# Stepper_Controller_Schematic.net
KiCad netlist of a schematic drawn in Altium Designer
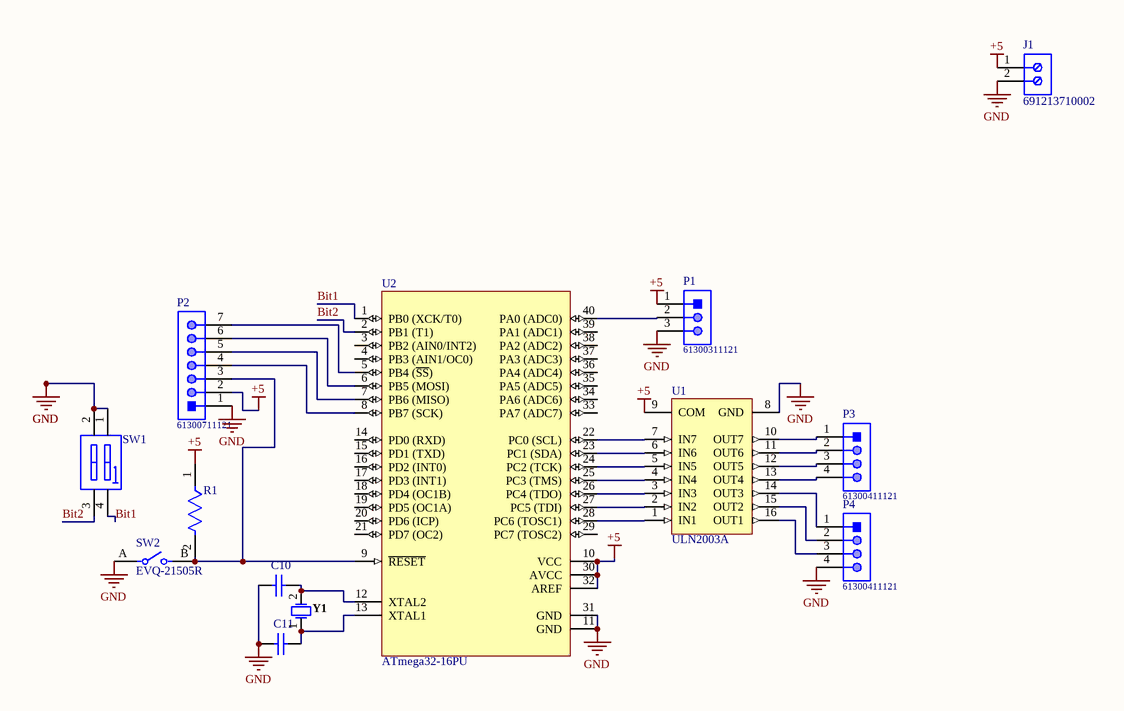
[diagram p0: Stepper Controller Schematic.SchDoc]

(export (version "E")
  (design (tool "Eeschema 10.0.6"))
  (components
    (comp (ref "C10")
      (value "~")
      (footprint "CAPR51-254-508X318X736")
      (libsource (lib "Altium Content Vault") (part "CAP-NP-2"))
    )
    (comp (ref "C11")
      (value "~")
      (footprint "CAPR51-254-508X318X736")
      (libsource (lib "Altium Content Vault") (part "CAP-NP-2"))
    )
    (comp (ref "J1")
      (value "691213710002")
      (footprint "691213710002")
      (description "Serie 213 - 5.00 mm Horizontal Entry Modular with RisingCage Clamp WR-TBL, 2 pin")
      (fields (field (name "MANUFACTURER") "Wurth Elektronik") (field (name "PUBLISHER") "WurthElektronik"))
      (libsource (lib "Altium Content Vault") (part "WE-CN-1P-F-TB2"))
    )
    (comp (ref "P1")
      (value "61300311121")
      (footprint "61300311121")
      (description "THT Vertical Pin Header WR-PHD, Pitch 2.54 mm, Single Row, 3 pins")
      (fields (field (name "MANUFACTURER") "Wurth Elektronik") (field (name "PUBLISHER") "WurthElektronik"))
      (libsource (lib "Altium Content Vault") (part "WE-CN-1P-M-R3"))
    )
    (comp (ref "P2")
      (value "61300711121")
      (footprint "61300711121")
      (description "THT Vertical Pin Header WR-PHD, Pitch 2.54 mm, Single Row, 7 pins")
      (fields (field (name "MANUFACTURER") "Wurth Elektronik") (field (name "PUBLISHER") "WurthElektronik"))
      (libsource (lib "Altium Content Vault") (part "WE-CN-1P-M-R7"))
    )
    (comp (ref "P3")
      (value "61300411121")
      (footprint "61300411121")
      (description "THT Vertical Pin Header WR-PHD, Pitch 2.54 mm, Single Row, 4 pins")
      (fields (field (name "MANUFACTURER") "Wurth Elektronik") (field (name "PUBLISHER") "WurthElektronik"))
      (libsource (lib "Altium Content Vault") (part "WE-CN-1P-M-R4"))
    )
    (comp (ref "P4")
      (value "61300411121")
      (footprint "61300411121")
      (description "THT Vertical Pin Header WR-PHD, Pitch 2.54 mm, Single Row, 4 pins")
      (fields (field (name "MANUFACTURER") "Wurth Elektronik") (field (name "PUBLISHER") "WurthElektronik"))
      (libsource (lib "Altium Content Vault") (part "WE-CN-1P-M-R4"))
    )
    (comp (ref "R1")
      (value "~")
      (footprint "FP-CF14-MFG")
      (description "RES 7.5K OHM 1/4W 5% AXIAL")
      (fields (field (name "TOLERANCE") "5%"))
      (libsource (lib "Altium Content Vault") (part "1029c3af85768c4190bb7ad29bc67b5"))
    )
    (comp (ref "SW1")
      (value "~")
      (footprint "418117270902")
      (description "WS-DITV 2.54 mm Compact THT Dip Switch with Raised Actuator")
      (fields (field (name "MANUFACTURER") "Wuerth Elektronik") (field (name "PARTNUMBER") "418117270902"))
      (libsource (lib "Altium Content Vault") (part "WE-DIP-SW-4"))
    )
    (comp (ref "SW2")
      (value "EVQ-21505R")
      (footprint "FP-EVQ-21505R-MFG")
      (description "SWITCH TACTILE SPST-NO 0.02A 15V")
      (libsource (lib "Altium Content Vault") (part "2b0b2b19372efd94fa7681498149756"))
    )
    (comp (ref "U1")
      (value "ULN2003A")
      (footprint "STM-DIP-16L")
      (description "Seven Darlington Array, 50 V, 0.5 A, -40 to 85 degC, 16-Pin DIP, RoHS, Tube")
      (fields (field (name "MANUFACTURER") "STMicroelectronics"))
      (libsource (lib "Altium Content Vault") (part "STM-ULN2003A-PDIP-16"))
    )
    (comp (ref "U2")
      (value "ATmega32-16PU")
      (footprint "40P6")
      (libsource (lib "Altium Content Vault") (part "MC-8B-ATM32-IL40"))
    )
    (comp (ref "Y1")
      (value "~")
      (footprint "FOX-FOXSLF160-20")
      (description "Resistance Weld Thru-Hole Crystal, 16 MHz, -20 to 70 degC, 2-Pin THD, RoHS, Bulk")
      (fields (field (name "TOLERANCE") "1%"))
      (libsource (lib "Altium Content Vault") (part "XTAL-1-2-2"))
    )
  )
  (nets
    (net (code "1") (name "+5") (class "Default")
      (node (ref "J1") (pin "1") (pinfunction "1_1") (pintype "passive"))
      (node (ref "P1") (pin "1") (pinfunction "1_1") (pintype "passive"))
      (node (ref "P2") (pin "2") (pinfunction "2_2") (pintype "passive"))
      (node (ref "R1") (pin "1") (pinfunction "1_1") (pintype "passive"))
      (node (ref "U1") (pin "9") (pinfunction "COM_9") (pintype "passive"))
      (node (ref "U2") (pin "10") (pinfunction "VCC_10") (pintype "power_in"))
      (node (ref "U2") (pin "30") (pinfunction "AVCC_30") (pintype "power_in"))
      (node (ref "U2") (pin "32") (pinfunction "AREF_32") (pintype "passive"))
    )
    (net (code "2") (name "/Bit1") (class "Default")
      (node (ref "SW1") (pin "4") (pinfunction "4_4") (pintype "passive"))
      (node (ref "U2") (pin "1") (pinfunction "PB0_(XCK/T0)_1") (pintype "bidirectional"))
    )
    (net (code "3") (name "/Bit2") (class "Default")
      (node (ref "SW1") (pin "3") (pinfunction "3_3") (pintype "passive"))
      (node (ref "U2") (pin "2") (pinfunction "PB1_(T1)_2") (pintype "bidirectional"))
    )
    (net (code "4") (name "GND") (class "Default")
      (node (ref "C10") (pin "1") (pinfunction "1_1") (pintype "passive"))
      (node (ref "C11") (pin "1") (pinfunction "1_1") (pintype "passive"))
      (node (ref "J1") (pin "2") (pinfunction "2_2") (pintype "passive"))
      (node (ref "P1") (pin "3") (pinfunction "3_3") (pintype "passive"))
      (node (ref "P2") (pin "1") (pinfunction "1_1") (pintype "passive"))
      (node (ref "P4") (pin "4") (pinfunction "4_4") (pintype "passive"))
      (node (ref "SW1") (pin "1") (pinfunction "1_1") (pintype "passive"))
      (node (ref "SW1") (pin "2") (pinfunction "2_2") (pintype "passive"))
      (node (ref "SW2") (pin "A") (pinfunction "A_A") (pintype "passive"))
      (node (ref "U1") (pin "8") (pinfunction "GND_8") (pintype "power_in"))
      (node (ref "U2") (pin "11") (pinfunction "GND_11") (pintype "power_in"))
      (node (ref "U2") (pin "31") (pinfunction "GND_31") (pintype "power_in"))
    )
    (net (code "5") (name "Net-(U1-IN1)") (class "Default")
      (node (ref "U1") (pin "1") (pinfunction "IN1_1") (pintype "input"))
      (node (ref "U2") (pin "28") (pinfunction "PC6_(TOSC1)_28") (pintype "bidirectional"))
    )
    (net (code "6") (name "Net-(U1-IN2)") (class "Default")
      (node (ref "U1") (pin "2") (pinfunction "IN2_2") (pintype "input"))
      (node (ref "U2") (pin "27") (pinfunction "PC5_(TDI)_27") (pintype "bidirectional"))
    )
    (net (code "7") (name "Net-(U1-IN3)") (class "Default")
      (node (ref "U1") (pin "3") (pinfunction "IN3_3") (pintype "input"))
      (node (ref "U2") (pin "26") (pinfunction "PC4_(TDO)_26") (pintype "bidirectional"))
    )
    (net (code "8") (name "Net-(U1-IN4)") (class "Default")
      (node (ref "U1") (pin "4") (pinfunction "IN4_4") (pintype "input"))
      (node (ref "U2") (pin "25") (pinfunction "PC3_(TMS)_25") (pintype "bidirectional"))
    )
    (net (code "9") (name "Net-(U1-IN5)") (class "Default")
      (node (ref "U1") (pin "5") (pinfunction "IN5_5") (pintype "input"))
      (node (ref "U2") (pin "24") (pinfunction "PC2_(TCK)_24") (pintype "bidirectional"))
    )
    (net (code "10") (name "Net-(U1-IN6)") (class "Default")
      (node (ref "U1") (pin "6") (pinfunction "IN6_6") (pintype "input"))
      (node (ref "U2") (pin "23") (pinfunction "PC1_(SDA)_23") (pintype "bidirectional"))
    )
    (net (code "11") (name "Net-(U1-IN7)") (class "Default")
      (node (ref "U1") (pin "7") (pinfunction "IN7_7") (pintype "input"))
      (node (ref "U2") (pin "22") (pinfunction "PC0_(SCL)_22") (pintype "bidirectional"))
    )
    (net (code "12") (name "Net-(U1-OUT1)") (class "Default")
      (node (ref "P4") (pin "3") (pinfunction "3_3") (pintype "passive"))
      (node (ref "U1") (pin "16") (pinfunction "OUT1_16") (pintype "output"))
    )
    (net (code "13") (name "Net-(U1-OUT2)") (class "Default")
      (node (ref "P4") (pin "2") (pinfunction "2_2") (pintype "passive"))
      (node (ref "U1") (pin "15") (pinfunction "OUT2_15") (pintype "output"))
    )
    (net (code "14") (name "Net-(U1-OUT3)") (class "Default")
      (node (ref "P4") (pin "1") (pinfunction "1_1") (pintype "passive"))
      (node (ref "U1") (pin "14") (pinfunction "OUT3_14") (pintype "output"))
    )
    (net (code "15") (name "Net-(U1-OUT4)") (class "Default")
      (node (ref "P3") (pin "4") (pinfunction "4_4") (pintype "passive"))
      (node (ref "U1") (pin "13") (pinfunction "OUT4_13") (pintype "output"))
    )
    (net (code "16") (name "Net-(U1-OUT5)") (class "Default")
      (node (ref "P3") (pin "3") (pinfunction "3_3") (pintype "passive"))
      (node (ref "U1") (pin "12") (pinfunction "OUT5_12") (pintype "output"))
    )
    (net (code "17") (name "Net-(U1-OUT6)") (class "Default")
      (node (ref "P3") (pin "2") (pinfunction "2_2") (pintype "passive"))
      (node (ref "U1") (pin "11") (pinfunction "OUT6_11") (pintype "output"))
    )
    (net (code "18") (name "Net-(U1-OUT7)") (class "Default")
      (node (ref "P3") (pin "1") (pinfunction "1_1") (pintype "passive"))
      (node (ref "U1") (pin "10") (pinfunction "OUT7_10") (pintype "output"))
    )
    (net (code "19") (name "Net-(U2-PA0_(ADC0))") (class "Default")
      (node (ref "P1") (pin "2") (pinfunction "2_2") (pintype "passive"))
      (node (ref "U2") (pin "40") (pinfunction "PA0_(ADC0)_40") (pintype "bidirectional"))
    )
    (net (code "20") (name "Net-(U2-PB4_(~{SS}))") (class "Default")
      (node (ref "P2") (pin "7") (pinfunction "7_7") (pintype "passive"))
      (node (ref "U2") (pin "5") (pinfunction "PB4_(~{SS})_5") (pintype "bidirectional"))
    )
    (net (code "21") (name "Net-(U2-PB5_(MOSI))") (class "Default")
      (node (ref "P2") (pin "6") (pinfunction "6_6") (pintype "passive"))
      (node (ref "U2") (pin "6") (pinfunction "PB5_(MOSI)_6") (pintype "bidirectional"))
    )
    (net (code "22") (name "Net-(U2-PB6_(MISO))") (class "Default")
      (node (ref "P2") (pin "5") (pinfunction "5_5") (pintype "passive"))
      (node (ref "U2") (pin "7") (pinfunction "PB6_(MISO)_7") (pintype "bidirectional"))
    )
    (net (code "23") (name "Net-(U2-PB7_(SCK))") (class "Default")
      (node (ref "P2") (pin "4") (pinfunction "4_4") (pintype "passive"))
      (node (ref "U2") (pin "8") (pinfunction "PB7_(SCK)_8") (pintype "bidirectional"))
    )
    (net (code "24") (name "Net-(U2-XTAL1)") (class "Default")
      (node (ref "C11") (pin "2") (pinfunction "2_2") (pintype "passive"))
      (node (ref "U2") (pin "13") (pinfunction "XTAL1_13") (pintype "passive"))
      (node (ref "Y1") (pin "1") (pinfunction "1_1") (pintype "passive"))
    )
    (net (code "25") (name "Net-(U2-XTAL2)") (class "Default")
      (node (ref "C10") (pin "2") (pinfunction "2_2") (pintype "passive"))
      (node (ref "U2") (pin "12") (pinfunction "XTAL2_12") (pintype "passive"))
      (node (ref "Y1") (pin "2") (pinfunction "2_2") (pintype "passive"))
    )
    (net (code "26") (name "Net-(U2-~{RESET})") (class "Default")
      (node (ref "P2") (pin "3") (pinfunction "3_3") (pintype "passive"))
      (node (ref "R1") (pin "2") (pinfunction "2_2") (pintype "passive"))
      (node (ref "SW2") (pin "B") (pinfunction "B_B") (pintype "passive"))
      (node (ref "U2") (pin "9") (pinfunction "~{RESET}_9") (pintype "input"))
    )
    (net (code "27") (name "unconnected-(U2-PA1_(ADC1)-Pad39)") (class "Default")
      (node (ref "U2") (pin "39") (pinfunction "PA1_(ADC1)_39") (pintype "bidirectional"))
    )
    (net (code "28") (name "unconnected-(U2-PA2_(ADC2)-Pad38)") (class "Default")
      (node (ref "U2") (pin "38") (pinfunction "PA2_(ADC2)_38") (pintype "bidirectional"))
    )
    (net (code "29") (name "unconnected-(U2-PA3_(ADC3)-Pad37)") (class "Default")
      (node (ref "U2") (pin "37") (pinfunction "PA3_(ADC3)_37") (pintype "bidirectional"))
    )
    (net (code "30") (name "unconnected-(U2-PA4_(ADC4)-Pad36)") (class "Default")
      (node (ref "U2") (pin "36") (pinfunction "PA4_(ADC4)_36") (pintype "bidirectional"))
    )
    (net (code "31") (name "unconnected-(U2-PA5_(ADC5)-Pad35)") (class "Default")
      (node (ref "U2") (pin "35") (pinfunction "PA5_(ADC5)_35") (pintype "bidirectional"))
    )
    (net (code "32") (name "unconnected-(U2-PA6_(ADC6)-Pad34)") (class "Default")
      (node (ref "U2") (pin "34") (pinfunction "PA6_(ADC6)_34") (pintype "bidirectional"))
    )
    (net (code "33") (name "unconnected-(U2-PA7_(ADC7)-Pad33)") (class "Default")
      (node (ref "U2") (pin "33") (pinfunction "PA7_(ADC7)_33") (pintype "bidirectional"))
    )
    (net (code "34") (name "unconnected-(U2-PB2_(AIN0{slash}INT2)-Pad3)") (class "Default")
      (node (ref "U2") (pin "3") (pinfunction "PB2_(AIN0/INT2)_3") (pintype "bidirectional"))
    )
    (net (code "35") (name "unconnected-(U2-PB3_(AIN1{slash}OC0)-Pad4)") (class "Default")
      (node (ref "U2") (pin "4") (pinfunction "PB3_(AIN1/OC0)_4") (pintype "bidirectional"))
    )
    (net (code "36") (name "unconnected-(U2-PC7_(TOSC2)-Pad29)") (class "Default")
      (node (ref "U2") (pin "29") (pinfunction "PC7_(TOSC2)_29") (pintype "bidirectional"))
    )
    (net (code "37") (name "unconnected-(U2-PD0_(RXD)-Pad14)") (class "Default")
      (node (ref "U2") (pin "14") (pinfunction "PD0_(RXD)_14") (pintype "bidirectional"))
    )
    (net (code "38") (name "unconnected-(U2-PD1_(TXD)-Pad15)") (class "Default")
      (node (ref "U2") (pin "15") (pinfunction "PD1_(TXD)_15") (pintype "bidirectional"))
    )
    (net (code "39") (name "unconnected-(U2-PD2_(INT0)-Pad16)") (class "Default")
      (node (ref "U2") (pin "16") (pinfunction "PD2_(INT0)_16") (pintype "bidirectional"))
    )
    (net (code "40") (name "unconnected-(U2-PD3_(INT1)-Pad17)") (class "Default")
      (node (ref "U2") (pin "17") (pinfunction "PD3_(INT1)_17") (pintype "bidirectional"))
    )
    (net (code "41") (name "unconnected-(U2-PD4_(OC1B)-Pad18)") (class "Default")
      (node (ref "U2") (pin "18") (pinfunction "PD4_(OC1B)_18") (pintype "bidirectional"))
    )
    (net (code "42") (name "unconnected-(U2-PD5_(OC1A)-Pad19)") (class "Default")
      (node (ref "U2") (pin "19") (pinfunction "PD5_(OC1A)_19") (pintype "bidirectional"))
    )
    (net (code "43") (name "unconnected-(U2-PD6_(ICP)-Pad20)") (class "Default")
      (node (ref "U2") (pin "20") (pinfunction "PD6_(ICP)_20") (pintype "bidirectional"))
    )
    (net (code "44") (name "unconnected-(U2-PD7_(OC2)-Pad21)") (class "Default")
      (node (ref "U2") (pin "21") (pinfunction "PD7_(OC2)_21") (pintype "bidirectional"))
    )
  )
)
